# PC_v1_double_layers.net
KiCad netlist of a schematic drawn in EAGLE
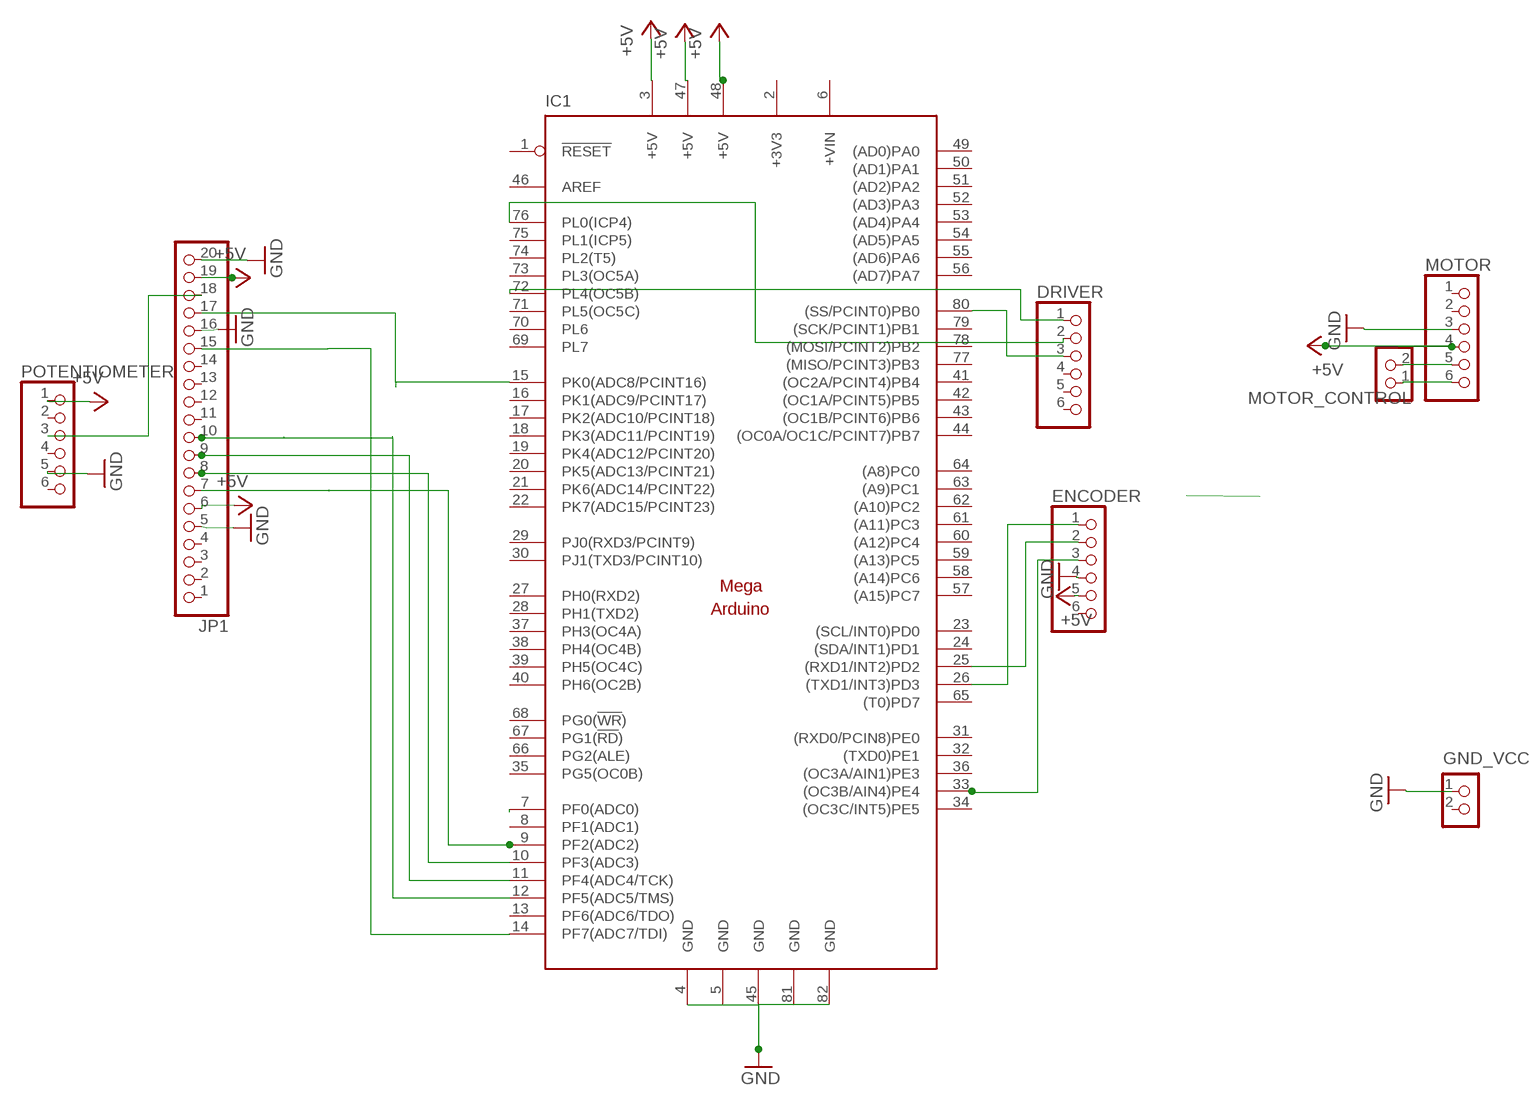
[diagram p0: schematic, sheet 1]

(export (version "E")
  (design (tool "Eeschema 10.0.6"))
  (components
    (comp (ref "DRIVER")
      (value "PINHD-1X6CLEAN")
      (footprint "eagle-import:1X06-CLEAN")
      (libsource (lib "eagle-import") (part "PINHD-1X6CLEAN"))
    )
    (comp (ref "ENCODER")
      (value "PINHD-1X6CLEAN")
      (footprint "eagle-import:1X06-CLEAN")
      (libsource (lib "eagle-import") (part "PINHD-1X6CLEAN"))
    )
    (comp (ref "GND_VCC")
      (value "CON_TERMINAL_BLOCK_02-5MM")
      (footprint "eagle-import:TERMINAL_BLOCK_2P_5")
      (libsource (lib "eagle-import") (part "CON_TERMINAL_BLOCK_02-5MM"))
    )
    (comp (ref "IC1")
      (value "MEGAARDUINO_1")
      (footprint "eagle-import:MEGA_ARDUINO")
      (libsource (lib "eagle-import") (part "MEGAARDUINO_1"))
    )
    (comp (ref "JP1")
      (value "PINHD-1X20")
      (footprint "eagle-import:1X20")
      (libsource (lib "eagle-import") (part "PINHD-1X20"))
    )
    (comp (ref "MOTOR")
      (value "PINHD-1X6CLEAN")
      (footprint "eagle-import:1X06-CLEAN")
      (libsource (lib "eagle-import") (part "PINHD-1X6CLEAN"))
    )
    (comp (ref "MOTOR_CONTROL")
      (value "CON_TERMINAL_BLOCK_02-5MM")
      (footprint "eagle-import:TERMINAL_BLOCK_2P_5")
      (libsource (lib "eagle-import") (part "CON_TERMINAL_BLOCK_02-5MM"))
    )
    (comp (ref "POTENTIOMETER")
      (value "PINHD-1X6CLEAN")
      (footprint "eagle-import:1X06-CLEAN")
      (libsource (lib "eagle-import") (part "PINHD-1X6CLEAN"))
    )
  )
  (nets
    (net (code "1") (name "+5V") (class "Default")
      (node (ref "ENCODER") (pin "5") (pinfunction "5_5") (pintype "passive"))
      (node (ref "IC1") (pin "3") (pinfunction "+5V_3") (pintype "power_in"))
      (node (ref "IC1") (pin "47") (pinfunction "+5V_47") (pintype "power_in"))
      (node (ref "IC1") (pin "48") (pinfunction "+5V_48") (pintype "power_in"))
      (node (ref "JP1") (pin "19") (pinfunction "19_19") (pintype "passive"))
      (node (ref "JP1") (pin "6") (pinfunction "6_6") (pintype "passive"))
      (node (ref "MOTOR") (pin "4") (pinfunction "4_4") (pintype "passive"))
      (node (ref "POTENTIOMETER") (pin "1") (pinfunction "1_1") (pintype "passive"))
    )
    (net (code "2") (name "/+3V3") (class "Default")
      (node (ref "IC1") (pin "2") (pinfunction "+3V3_2") (pintype "power_in"))
    )
    (net (code "3") (name "/+VIN") (class "Default")
      (node (ref "IC1") (pin "6") (pinfunction "+VIN_6") (pintype "power_in"))
    )
    (net (code "4") (name "GND") (class "Default")
      (node (ref "ENCODER") (pin "4") (pinfunction "4_4") (pintype "passive"))
      (node (ref "GND_VCC") (pin "1") (pinfunction "1_1") (pintype "passive"))
      (node (ref "IC1") (pin "4") (pinfunction "GND_4") (pintype "power_in"))
      (node (ref "IC1") (pin "45") (pinfunction "GND_45") (pintype "power_in"))
      (node (ref "IC1") (pin "5") (pinfunction "GND_5") (pintype "power_in"))
      (node (ref "IC1") (pin "81") (pinfunction "GND_81") (pintype "power_in"))
      (node (ref "IC1") (pin "82") (pinfunction "GND_82") (pintype "power_in"))
      (node (ref "JP1") (pin "16") (pinfunction "16_16") (pintype "passive"))
      (node (ref "JP1") (pin "20") (pinfunction "20_20") (pintype "passive"))
      (node (ref "JP1") (pin "5") (pinfunction "5_5") (pintype "passive"))
      (node (ref "MOTOR") (pin "3") (pinfunction "3_3") (pintype "passive"))
      (node (ref "POTENTIOMETER") (pin "5") (pinfunction "5_5") (pintype "passive"))
    )
    (net (code "5") (name "Net-(IC1-(OC3B{slash}AIN4)PE4)") (class "Default")
      (node (ref "ENCODER") (pin "3") (pinfunction "3_3") (pintype "passive"))
      (node (ref "IC1") (pin "33") (pinfunction "(OC3B/AIN4)PE4_33") (pintype "bidirectional"))
    )
    (net (code "6") (name "Net-(IC1-(RXD1{slash}INT2)PD2)") (class "Default")
      (node (ref "ENCODER") (pin "2") (pinfunction "2_2") (pintype "passive"))
      (node (ref "IC1") (pin "25") (pinfunction "(RXD1/INT2)PD2_25") (pintype "bidirectional"))
    )
    (net (code "7") (name "Net-(IC1-(SS{slash}PCINT0)PB0)") (class "Default")
      (node (ref "DRIVER") (pin "3") (pinfunction "3_3") (pintype "passive"))
      (node (ref "IC1") (pin "80") (pinfunction "(SS/PCINT0)PB0_80") (pintype "bidirectional"))
    )
    (net (code "8") (name "Net-(IC1-(TXD1{slash}INT3)PD3)") (class "Default")
      (node (ref "ENCODER") (pin "1") (pinfunction "1_1") (pintype "passive"))
      (node (ref "IC1") (pin "26") (pinfunction "(TXD1/INT3)PD3_26") (pintype "bidirectional"))
    )
    (net (code "9") (name "Net-(IC1-PF2(ADC2))") (class "Default")
      (node (ref "IC1") (pin "9") (pinfunction "PF2(ADC2)_9") (pintype "bidirectional"))
      (node (ref "JP1") (pin "7") (pinfunction "7_7") (pintype "passive"))
    )
    (net (code "10") (name "Net-(IC1-PF3(ADC3))") (class "Default")
      (node (ref "IC1") (pin "10") (pinfunction "PF3(ADC3)_10") (pintype "bidirectional"))
      (node (ref "JP1") (pin "8") (pinfunction "8_8") (pintype "passive"))
    )
    (net (code "11") (name "Net-(IC1-PF4(ADC4{slash}TCK))") (class "Default")
      (node (ref "IC1") (pin "11") (pinfunction "PF4(ADC4/TCK)_11") (pintype "bidirectional"))
      (node (ref "JP1") (pin "9") (pinfunction "9_9") (pintype "passive"))
    )
    (net (code "12") (name "Net-(IC1-PF5(ADC5{slash}TMS))") (class "Default")
      (node (ref "IC1") (pin "12") (pinfunction "PF5(ADC5/TMS)_12") (pintype "bidirectional"))
      (node (ref "JP1") (pin "10") (pinfunction "10_10") (pintype "passive"))
    )
    (net (code "13") (name "Net-(IC1-PF7(ADC7{slash}TDI))") (class "Default")
      (node (ref "IC1") (pin "14") (pinfunction "PF7(ADC7/TDI)_14") (pintype "bidirectional"))
      (node (ref "JP1") (pin "15") (pinfunction "15_15") (pintype "passive"))
    )
    (net (code "14") (name "Net-(IC1-PK0(ADC8{slash}PCINT16))") (class "Default")
      (node (ref "IC1") (pin "15") (pinfunction "PK0(ADC8/PCINT16)_15") (pintype "bidirectional"))
      (node (ref "JP1") (pin "17") (pinfunction "17_17") (pintype "passive"))
    )
    (net (code "15") (name "Net-(IC1-PL0(ICP4))") (class "Default")
      (node (ref "DRIVER") (pin "2") (pinfunction "2_2") (pintype "passive"))
      (node (ref "IC1") (pin "76") (pinfunction "PL0(ICP4)_76") (pintype "bidirectional"))
    )
    (net (code "16") (name "Net-(IC1-PL4(OC5B))") (class "Default")
      (node (ref "DRIVER") (pin "1") (pinfunction "1_1") (pintype "passive"))
      (node (ref "IC1") (pin "72") (pinfunction "PL4(OC5B)_72") (pintype "bidirectional"))
    )
    (net (code "17") (name "Net-(JP1-Pad18)") (class "Default")
      (node (ref "JP1") (pin "18") (pinfunction "18_18") (pintype "passive"))
      (node (ref "POTENTIOMETER") (pin "3") (pinfunction "3_3") (pintype "passive"))
    )
    (net (code "18") (name "Net-(MOTOR-Pad5)") (class "Default")
      (node (ref "MOTOR") (pin "5") (pinfunction "5_5") (pintype "passive"))
      (node (ref "MOTOR_CONTROL") (pin "2") (pinfunction "2_2") (pintype "passive"))
    )
    (net (code "19") (name "Net-(MOTOR-Pad6)") (class "Default")
      (node (ref "MOTOR") (pin "6") (pinfunction "6_6") (pintype "passive"))
      (node (ref "MOTOR_CONTROL") (pin "1") (pinfunction "1_1") (pintype "passive"))
    )
    (net (code "20") (name "unconnected-(DRIVER-Pad4)") (class "Default")
      (node (ref "DRIVER") (pin "4") (pinfunction "4_4") (pintype "passive"))
    )
    (net (code "21") (name "unconnected-(DRIVER-Pad5)") (class "Default")
      (node (ref "DRIVER") (pin "5") (pinfunction "5_5") (pintype "passive"))
    )
    (net (code "22") (name "unconnected-(DRIVER-Pad6)") (class "Default")
      (node (ref "DRIVER") (pin "6") (pinfunction "6_6") (pintype "passive"))
    )
    (net (code "23") (name "unconnected-(ENCODER-Pad6)") (class "Default")
      (node (ref "ENCODER") (pin "6") (pinfunction "6_6") (pintype "passive"))
    )
    (net (code "24") (name "unconnected-(GND_VCC-Pad2)") (class "Default")
      (node (ref "GND_VCC") (pin "2") (pinfunction "2_2") (pintype "passive"))
    )
    (net (code "25") (name "unconnected-(IC1-(A8)PC0-Pad64)") (class "Default")
      (node (ref "IC1") (pin "64") (pinfunction "(A8)PC0_64") (pintype "bidirectional"))
    )
    (net (code "26") (name "unconnected-(IC1-(A9)PC1-Pad63)") (class "Default")
      (node (ref "IC1") (pin "63") (pinfunction "(A9)PC1_63") (pintype "bidirectional"))
    )
    (net (code "27") (name "unconnected-(IC1-(A10)PC2-Pad62)") (class "Default")
      (node (ref "IC1") (pin "62") (pinfunction "(A10)PC2_62") (pintype "bidirectional"))
    )
    (net (code "28") (name "unconnected-(IC1-(A11)PC3-Pad61)") (class "Default")
      (node (ref "IC1") (pin "61") (pinfunction "(A11)PC3_61") (pintype "bidirectional"))
    )
    (net (code "29") (name "unconnected-(IC1-(A12)PC4-Pad60)") (class "Default")
      (node (ref "IC1") (pin "60") (pinfunction "(A12)PC4_60") (pintype "bidirectional"))
    )
    (net (code "30") (name "unconnected-(IC1-(A13)PC5-Pad59)") (class "Default")
      (node (ref "IC1") (pin "59") (pinfunction "(A13)PC5_59") (pintype "bidirectional"))
    )
    (net (code "31") (name "unconnected-(IC1-(A14)PC6-Pad58)") (class "Default")
      (node (ref "IC1") (pin "58") (pinfunction "(A14)PC6_58") (pintype "bidirectional"))
    )
    (net (code "32") (name "unconnected-(IC1-(A15)PC7-Pad57)") (class "Default")
      (node (ref "IC1") (pin "57") (pinfunction "(A15)PC7_57") (pintype "bidirectional"))
    )
    (net (code "33") (name "unconnected-(IC1-(AD0)PA0-Pad49)") (class "Default")
      (node (ref "IC1") (pin "49") (pinfunction "(AD0)PA0_49") (pintype "bidirectional"))
    )
    (net (code "34") (name "unconnected-(IC1-(AD1)PA1-Pad50)") (class "Default")
      (node (ref "IC1") (pin "50") (pinfunction "(AD1)PA1_50") (pintype "bidirectional"))
    )
    (net (code "35") (name "unconnected-(IC1-(AD2)PA2-Pad51)") (class "Default")
      (node (ref "IC1") (pin "51") (pinfunction "(AD2)PA2_51") (pintype "bidirectional"))
    )
    (net (code "36") (name "unconnected-(IC1-(AD3)PA3-Pad52)") (class "Default")
      (node (ref "IC1") (pin "52") (pinfunction "(AD3)PA3_52") (pintype "bidirectional"))
    )
    (net (code "37") (name "unconnected-(IC1-(AD4)PA4-Pad53)") (class "Default")
      (node (ref "IC1") (pin "53") (pinfunction "(AD4)PA4_53") (pintype "bidirectional"))
    )
    (net (code "38") (name "unconnected-(IC1-(AD5)PA5-Pad54)") (class "Default")
      (node (ref "IC1") (pin "54") (pinfunction "(AD5)PA5_54") (pintype "bidirectional"))
    )
    (net (code "39") (name "unconnected-(IC1-(AD6)PA6-Pad55)") (class "Default")
      (node (ref "IC1") (pin "55") (pinfunction "(AD6)PA6_55") (pintype "bidirectional"))
    )
    (net (code "40") (name "unconnected-(IC1-(AD7)PA7-Pad56)") (class "Default")
      (node (ref "IC1") (pin "56") (pinfunction "(AD7)PA7_56") (pintype "bidirectional"))
    )
    (net (code "41") (name "unconnected-(IC1-(MISO{slash}PCINT3)PB3-Pad77)") (class "Default")
      (node (ref "IC1") (pin "77") (pinfunction "(MISO/PCINT3)PB3_77") (pintype "bidirectional"))
    )
    (net (code "42") (name "unconnected-(IC1-(MOSI{slash}PCINT2)PB2-Pad78)") (class "Default")
      (node (ref "IC1") (pin "78") (pinfunction "(MOSI/PCINT2)PB2_78") (pintype "bidirectional"))
    )
    (net (code "43") (name "unconnected-(IC1-(OC0A{slash}OC1C{slash}PCINT7)PB7-Pad44)") (class "Default")
      (node (ref "IC1") (pin "44") (pinfunction "(OC0A/OC1C/PCINT7)PB7_44") (pintype "bidirectional"))
    )
    (net (code "44") (name "unconnected-(IC1-(OC1A{slash}PCINT5)PB5-Pad42)") (class "Default")
      (node (ref "IC1") (pin "42") (pinfunction "(OC1A/PCINT5)PB5_42") (pintype "bidirectional"))
    )
    (net (code "45") (name "unconnected-(IC1-(OC1B{slash}PCINT6)PB6-Pad43)") (class "Default")
      (node (ref "IC1") (pin "43") (pinfunction "(OC1B/PCINT6)PB6_43") (pintype "bidirectional"))
    )
    (net (code "46") (name "unconnected-(IC1-(OC2A{slash}PCINT4)PB4-Pad41)") (class "Default")
      (node (ref "IC1") (pin "41") (pinfunction "(OC2A/PCINT4)PB4_41") (pintype "bidirectional"))
    )
    (net (code "47") (name "unconnected-(IC1-(OC3A{slash}AIN1)PE3-Pad36)") (class "Default")
      (node (ref "IC1") (pin "36") (pinfunction "(OC3A/AIN1)PE3_36") (pintype "bidirectional"))
    )
    (net (code "48") (name "unconnected-(IC1-(OC3C{slash}INT5)PE5-Pad34)") (class "Default")
      (node (ref "IC1") (pin "34") (pinfunction "(OC3C/INT5)PE5_34") (pintype "bidirectional"))
    )
    (net (code "49") (name "unconnected-(IC1-(RXD0{slash}PCIN8)PE0-Pad31)") (class "Default")
      (node (ref "IC1") (pin "31") (pinfunction "(RXD0/PCIN8)PE0_31") (pintype "bidirectional"))
    )
    (net (code "50") (name "unconnected-(IC1-(SCK{slash}PCINT1)PB1-Pad79)") (class "Default")
      (node (ref "IC1") (pin "79") (pinfunction "(SCK/PCINT1)PB1_79") (pintype "bidirectional"))
    )
    (net (code "51") (name "unconnected-(IC1-(SCL{slash}INT0)PD0-Pad23)") (class "Default")
      (node (ref "IC1") (pin "23") (pinfunction "(SCL/INT0)PD0_23") (pintype "bidirectional"))
    )
    (net (code "52") (name "unconnected-(IC1-(SDA{slash}INT1)PD1-Pad24)") (class "Default")
      (node (ref "IC1") (pin "24") (pinfunction "(SDA/INT1)PD1_24") (pintype "bidirectional"))
    )
    (net (code "53") (name "unconnected-(IC1-(T0)PD7-Pad65)") (class "Default")
      (node (ref "IC1") (pin "65") (pinfunction "(T0)PD7_65") (pintype "bidirectional"))
    )
    (net (code "54") (name "unconnected-(IC1-(TXD0)PE1-Pad32)") (class "Default")
      (node (ref "IC1") (pin "32") (pinfunction "(TXD0)PE1_32") (pintype "bidirectional"))
    )
    (net (code "55") (name "unconnected-(IC1-AREF-Pad46)") (class "Default")
      (node (ref "IC1") (pin "46") (pinfunction "AREF_46") (pintype "bidirectional"))
    )
    (net (code "56") (name "unconnected-(IC1-PF0(ADC0)-Pad7)") (class "Default")
      (node (ref "IC1") (pin "7") (pinfunction "PF0(ADC0)_7") (pintype "bidirectional"))
    )
    (net (code "57") (name "unconnected-(IC1-PF1(ADC1)-Pad8)") (class "Default")
      (node (ref "IC1") (pin "8") (pinfunction "PF1(ADC1)_8") (pintype "bidirectional"))
    )
    (net (code "58") (name "unconnected-(IC1-PF6(ADC6{slash}TDO)-Pad13)") (class "Default")
      (node (ref "IC1") (pin "13") (pinfunction "PF6(ADC6/TDO)_13") (pintype "bidirectional"))
    )
    (net (code "59") (name "unconnected-(IC1-PG0(~{WR})-Pad68)") (class "Default")
      (node (ref "IC1") (pin "68") (pinfunction "PG0(~{WR})_68") (pintype "bidirectional"))
    )
    (net (code "60") (name "unconnected-(IC1-PG1(~{RD})-Pad67)") (class "Default")
      (node (ref "IC1") (pin "67") (pinfunction "PG1(~{RD})_67") (pintype "bidirectional"))
    )
    (net (code "61") (name "unconnected-(IC1-PG2(ALE)-Pad66)") (class "Default")
      (node (ref "IC1") (pin "66") (pinfunction "PG2(ALE)_66") (pintype "bidirectional"))
    )
    (net (code "62") (name "unconnected-(IC1-PG5(OC0B)-Pad35)") (class "Default")
      (node (ref "IC1") (pin "35") (pinfunction "PG5(OC0B)_35") (pintype "bidirectional"))
    )
    (net (code "63") (name "unconnected-(IC1-PH0(RXD2)-Pad27)") (class "Default")
      (node (ref "IC1") (pin "27") (pinfunction "PH0(RXD2)_27") (pintype "bidirectional"))
    )
    (net (code "64") (name "unconnected-(IC1-PH1(TXD2)-Pad28)") (class "Default")
      (node (ref "IC1") (pin "28") (pinfunction "PH1(TXD2)_28") (pintype "bidirectional"))
    )
    (net (code "65") (name "unconnected-(IC1-PH3(OC4A)-Pad37)") (class "Default")
      (node (ref "IC1") (pin "37") (pinfunction "PH3(OC4A)_37") (pintype "bidirectional"))
    )
    (net (code "66") (name "unconnected-(IC1-PH4(OC4B)-Pad38)") (class "Default")
      (node (ref "IC1") (pin "38") (pinfunction "PH4(OC4B)_38") (pintype "bidirectional"))
    )
    (net (code "67") (name "unconnected-(IC1-PH5(OC4C)-Pad39)") (class "Default")
      (node (ref "IC1") (pin "39") (pinfunction "PH5(OC4C)_39") (pintype "bidirectional"))
    )
    (net (code "68") (name "unconnected-(IC1-PH6(OC2B)-Pad40)") (class "Default")
      (node (ref "IC1") (pin "40") (pinfunction "PH6(OC2B)_40") (pintype "bidirectional"))
    )
    (net (code "69") (name "unconnected-(IC1-PJ0(RXD3{slash}PCINT9)-Pad29)") (class "Default")
      (node (ref "IC1") (pin "29") (pinfunction "PJ0(RXD3/PCINT9)_29") (pintype "bidirectional"))
    )
    (net (code "70") (name "unconnected-(IC1-PJ1(TXD3{slash}PCINT10)-Pad30)") (class "Default")
      (node (ref "IC1") (pin "30") (pinfunction "PJ1(TXD3/PCINT10)_30") (pintype "bidirectional"))
    )
    (net (code "71") (name "unconnected-(IC1-PK1(ADC9{slash}PCINT17)-Pad16)") (class "Default")
      (node (ref "IC1") (pin "16") (pinfunction "PK1(ADC9/PCINT17)_16") (pintype "bidirectional"))
    )
    (net (code "72") (name "unconnected-(IC1-PK2(ADC10{slash}PCINT18)-Pad17)") (class "Default")
      (node (ref "IC1") (pin "17") (pinfunction "PK2(ADC10/PCINT18)_17") (pintype "bidirectional"))
    )
    (net (code "73") (name "unconnected-(IC1-PK3(ADC11{slash}PCINT19)-Pad18)") (class "Default")
      (node (ref "IC1") (pin "18") (pinfunction "PK3(ADC11/PCINT19)_18") (pintype "bidirectional"))
    )
    (net (code "74") (name "unconnected-(IC1-PK4(ADC12{slash}PCINT20)-Pad19)") (class "Default")
      (node (ref "IC1") (pin "19") (pinfunction "PK4(ADC12/PCINT20)_19") (pintype "bidirectional"))
    )
    (net (code "75") (name "unconnected-(IC1-PK5(ADC13{slash}PCINT21)-Pad20)") (class "Default")
      (node (ref "IC1") (pin "20") (pinfunction "PK5(ADC13/PCINT21)_20") (pintype "bidirectional"))
    )
    (net (code "76") (name "unconnected-(IC1-PK6(ADC14{slash}PCINT22)-Pad21)") (class "Default")
      (node (ref "IC1") (pin "21") (pinfunction "PK6(ADC14/PCINT22)_21") (pintype "bidirectional"))
    )
    (net (code "77") (name "unconnected-(IC1-PK7(ADC15{slash}PCINT23)-Pad22)") (class "Default")
      (node (ref "IC1") (pin "22") (pinfunction "PK7(ADC15/PCINT23)_22") (pintype "bidirectional"))
    )
    (net (code "78") (name "unconnected-(IC1-PL1(ICP5)-Pad75)") (class "Default")
      (node (ref "IC1") (pin "75") (pinfunction "PL1(ICP5)_75") (pintype "bidirectional"))
    )
    (net (code "79") (name "unconnected-(IC1-PL2(T5)-Pad74)") (class "Default")
      (node (ref "IC1") (pin "74") (pinfunction "PL2(T5)_74") (pintype "bidirectional"))
    )
    (net (code "80") (name "unconnected-(IC1-PL3(OC5A)-Pad73)") (class "Default")
      (node (ref "IC1") (pin "73") (pinfunction "PL3(OC5A)_73") (pintype "bidirectional"))
    )
    (net (code "81") (name "unconnected-(IC1-PL5(OC5C)-Pad71)") (class "Default")
      (node (ref "IC1") (pin "71") (pinfunction "PL5(OC5C)_71") (pintype "bidirectional"))
    )
    (net (code "82") (name "unconnected-(IC1-PL6-Pad70)") (class "Default")
      (node (ref "IC1") (pin "70") (pinfunction "PL6_70") (pintype "bidirectional"))
    )
    (net (code "83") (name "unconnected-(IC1-PL7-Pad69)") (class "Default")
      (node (ref "IC1") (pin "69") (pinfunction "PL7_69") (pintype "bidirectional"))
    )
    (net (code "84") (name "unconnected-(IC1-~{RESET}-Pad1)") (class "Default")
      (node (ref "IC1") (pin "1") (pinfunction "~{RESET}_1") (pintype "bidirectional"))
    )
    (net (code "85") (name "unconnected-(JP1-Pad1)") (class "Default")
      (node (ref "JP1") (pin "1") (pinfunction "1_1") (pintype "passive"))
    )
    (net (code "86") (name "unconnected-(JP1-Pad2)") (class "Default")
      (node (ref "JP1") (pin "2") (pinfunction "2_2") (pintype "passive"))
    )
    (net (code "87") (name "unconnected-(JP1-Pad3)") (class "Default")
      (node (ref "JP1") (pin "3") (pinfunction "3_3") (pintype "passive"))
    )
    (net (code "88") (name "unconnected-(JP1-Pad4)") (class "Default")
      (node (ref "JP1") (pin "4") (pinfunction "4_4") (pintype "passive"))
    )
    (net (code "89") (name "unconnected-(JP1-Pad11)") (class "Default")
      (node (ref "JP1") (pin "11") (pinfunction "11_11") (pintype "passive"))
    )
    (net (code "90") (name "unconnected-(JP1-Pad12)") (class "Default")
      (node (ref "JP1") (pin "12") (pinfunction "12_12") (pintype "passive"))
    )
    (net (code "91") (name "unconnected-(JP1-Pad13)") (class "Default")
      (node (ref "JP1") (pin "13") (pinfunction "13_13") (pintype "passive"))
    )
    (net (code "92") (name "unconnected-(JP1-Pad14)") (class "Default")
      (node (ref "JP1") (pin "14") (pinfunction "14_14") (pintype "passive"))
    )
    (net (code "93") (name "unconnected-(MOTOR-Pad1)") (class "Default")
      (node (ref "MOTOR") (pin "1") (pinfunction "1_1") (pintype "passive"))
    )
    (net (code "94") (name "unconnected-(MOTOR-Pad2)") (class "Default")
      (node (ref "MOTOR") (pin "2") (pinfunction "2_2") (pintype "passive"))
    )
    (net (code "95") (name "unconnected-(POTENTIOMETER-Pad2)") (class "Default")
      (node (ref "POTENTIOMETER") (pin "2") (pinfunction "2_2") (pintype "passive"))
    )
    (net (code "96") (name "unconnected-(POTENTIOMETER-Pad4)") (class "Default")
      (node (ref "POTENTIOMETER") (pin "4") (pinfunction "4_4") (pintype "passive"))
    )
    (net (code "97") (name "unconnected-(POTENTIOMETER-Pad6)") (class "Default")
      (node (ref "POTENTIOMETER") (pin "6") (pinfunction "6_6") (pintype "passive"))
    )
  )
)
